# pvbconnector.net
KiCad netlist of a schematic drawn in EAGLE
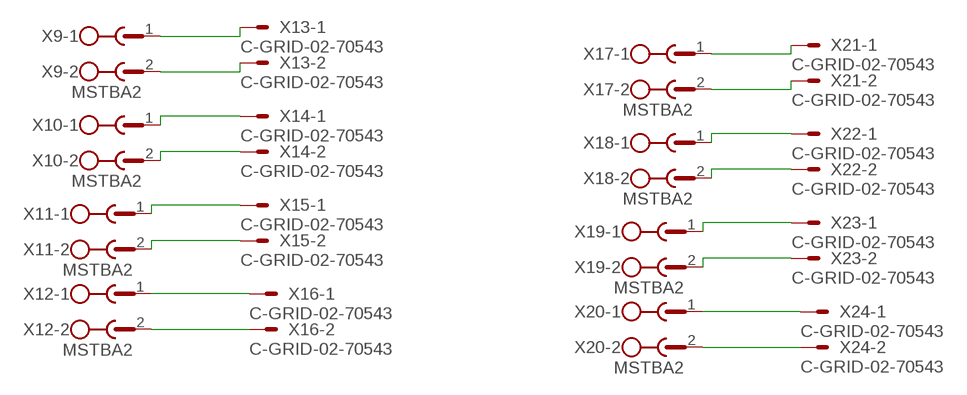
[diagram p0: schematic, sheet 1]

(export (version "E")
  (design (tool "Eeschema 10.0.6"))
  (components
    (comp (ref "X9")
      (value "MSTBA2")
      (footprint "eagle-import:MSTBA2")
      (fields (field (name "MF") "FARNELL") (field (name "MPN") "1757242"))
      (libsource (lib "eagle-import") (part "MSTBA2"))
    )
    (comp (ref "X10")
      (value "MSTBA2")
      (footprint "eagle-import:MSTBA2")
      (fields (field (name "MF") "FARNELL") (field (name "MPN") "1757242"))
      (libsource (lib "eagle-import") (part "MSTBA2"))
    )
    (comp (ref "X11")
      (value "MSTBA2")
      (footprint "eagle-import:MSTBA2")
      (fields (field (name "MF") "FARNELL") (field (name "MPN") "1757242"))
      (libsource (lib "eagle-import") (part "MSTBA2"))
    )
    (comp (ref "X12")
      (value "MSTBA2")
      (footprint "eagle-import:MSTBA2")
      (fields (field (name "MF") "FARNELL") (field (name "MPN") "1757242"))
      (libsource (lib "eagle-import") (part "MSTBA2"))
    )
    (comp (ref "X13")
      (value "C-GRID-02-70543")
      (footprint "eagle-import:70543-02")
      (fields (field (name "MF") "MOLEX"))
      (libsource (lib "eagle-import") (part "C-GRID-02-70543"))
    )
    (comp (ref "X14")
      (value "C-GRID-02-70543")
      (footprint "eagle-import:70543-02")
      (fields (field (name "MF") "MOLEX"))
      (libsource (lib "eagle-import") (part "C-GRID-02-70543"))
    )
    (comp (ref "X15")
      (value "C-GRID-02-70543")
      (footprint "eagle-import:70543-02")
      (fields (field (name "MF") "MOLEX"))
      (libsource (lib "eagle-import") (part "C-GRID-02-70543"))
    )
    (comp (ref "X16")
      (value "C-GRID-02-70543")
      (footprint "eagle-import:70543-02")
      (fields (field (name "MF") "MOLEX"))
      (libsource (lib "eagle-import") (part "C-GRID-02-70543"))
    )
    (comp (ref "X17")
      (value "MSTBA2")
      (footprint "eagle-import:MSTBA2")
      (fields (field (name "MF") "FARNELL") (field (name "MPN") "1757242"))
      (libsource (lib "eagle-import") (part "MSTBA2"))
    )
    (comp (ref "X18")
      (value "MSTBA2")
      (footprint "eagle-import:MSTBA2")
      (fields (field (name "MF") "FARNELL") (field (name "MPN") "1757242"))
      (libsource (lib "eagle-import") (part "MSTBA2"))
    )
    (comp (ref "X19")
      (value "MSTBA2")
      (footprint "eagle-import:MSTBA2")
      (fields (field (name "MF") "FARNELL") (field (name "MPN") "1757242"))
      (libsource (lib "eagle-import") (part "MSTBA2"))
    )
    (comp (ref "X20")
      (value "MSTBA2")
      (footprint "eagle-import:MSTBA2")
      (fields (field (name "MF") "FARNELL") (field (name "MPN") "1757242"))
      (libsource (lib "eagle-import") (part "MSTBA2"))
    )
    (comp (ref "X21")
      (value "C-GRID-02-70543")
      (footprint "eagle-import:70543-02")
      (fields (field (name "MF") "MOLEX"))
      (libsource (lib "eagle-import") (part "C-GRID-02-70543"))
    )
    (comp (ref "X22")
      (value "C-GRID-02-70543")
      (footprint "eagle-import:70543-02")
      (fields (field (name "MF") "MOLEX"))
      (libsource (lib "eagle-import") (part "C-GRID-02-70543"))
    )
    (comp (ref "X23")
      (value "C-GRID-02-70543")
      (footprint "eagle-import:70543-02")
      (fields (field (name "MF") "MOLEX"))
      (libsource (lib "eagle-import") (part "C-GRID-02-70543"))
    )
    (comp (ref "X24")
      (value "C-GRID-02-70543")
      (footprint "eagle-import:70543-02")
      (fields (field (name "MF") "MOLEX"))
      (libsource (lib "eagle-import") (part "C-GRID-02-70543"))
    )
  )
  (nets
    (net (code "1") (name "Net-(X10B-1)") (class "Default")
      (node (ref "X10") (pin "2") (pinfunction "1_2") (pintype "passive"))
      (node (ref "X14") (pin "2") (pinfunction "S_2") (pintype "passive"))
    )
    (net (code "2") (name "Net-(X11B-1)") (class "Default")
      (node (ref "X11") (pin "2") (pinfunction "1_2") (pintype "passive"))
      (node (ref "X15") (pin "2") (pinfunction "S_2") (pintype "passive"))
    )
    (net (code "3") (name "Net-(X12B-1)") (class "Default")
      (node (ref "X12") (pin "2") (pinfunction "1_2") (pintype "passive"))
      (node (ref "X16") (pin "2") (pinfunction "S_2") (pintype "passive"))
    )
    (net (code "4") (name "Net-(X13A-S)") (class "Default")
      (node (ref "X13") (pin "1") (pinfunction "S_1") (pintype "passive"))
      (node (ref "X9") (pin "1") (pinfunction "1_1") (pintype "passive"))
    )
    (net (code "5") (name "Net-(X13B-S)") (class "Default")
      (node (ref "X13") (pin "2") (pinfunction "S_2") (pintype "passive"))
      (node (ref "X9") (pin "2") (pinfunction "1_2") (pintype "passive"))
    )
    (net (code "6") (name "Net-(X14A-S)") (class "Default")
      (node (ref "X10") (pin "1") (pinfunction "1_1") (pintype "passive"))
      (node (ref "X14") (pin "1") (pinfunction "S_1") (pintype "passive"))
    )
    (net (code "7") (name "Net-(X15A-S)") (class "Default")
      (node (ref "X11") (pin "1") (pinfunction "1_1") (pintype "passive"))
      (node (ref "X15") (pin "1") (pinfunction "S_1") (pintype "passive"))
    )
    (net (code "8") (name "Net-(X16A-S)") (class "Default")
      (node (ref "X12") (pin "1") (pinfunction "1_1") (pintype "passive"))
      (node (ref "X16") (pin "1") (pinfunction "S_1") (pintype "passive"))
    )
    (net (code "9") (name "Net-(X17B-1)") (class "Default")
      (node (ref "X17") (pin "2") (pinfunction "1_2") (pintype "passive"))
      (node (ref "X21") (pin "2") (pinfunction "S_2") (pintype "passive"))
    )
    (net (code "10") (name "Net-(X18B-1)") (class "Default")
      (node (ref "X18") (pin "2") (pinfunction "1_2") (pintype "passive"))
      (node (ref "X22") (pin "2") (pinfunction "S_2") (pintype "passive"))
    )
    (net (code "11") (name "Net-(X19B-1)") (class "Default")
      (node (ref "X19") (pin "2") (pinfunction "1_2") (pintype "passive"))
      (node (ref "X23") (pin "2") (pinfunction "S_2") (pintype "passive"))
    )
    (net (code "12") (name "Net-(X20B-1)") (class "Default")
      (node (ref "X20") (pin "2") (pinfunction "1_2") (pintype "passive"))
      (node (ref "X24") (pin "2") (pinfunction "S_2") (pintype "passive"))
    )
    (net (code "13") (name "Net-(X21A-S)") (class "Default")
      (node (ref "X17") (pin "1") (pinfunction "1_1") (pintype "passive"))
      (node (ref "X21") (pin "1") (pinfunction "S_1") (pintype "passive"))
    )
    (net (code "14") (name "Net-(X22A-S)") (class "Default")
      (node (ref "X18") (pin "1") (pinfunction "1_1") (pintype "passive"))
      (node (ref "X22") (pin "1") (pinfunction "S_1") (pintype "passive"))
    )
    (net (code "15") (name "Net-(X23A-S)") (class "Default")
      (node (ref "X19") (pin "1") (pinfunction "1_1") (pintype "passive"))
      (node (ref "X23") (pin "1") (pinfunction "S_1") (pintype "passive"))
    )
    (net (code "16") (name "Net-(X24A-S)") (class "Default")
      (node (ref "X20") (pin "1") (pinfunction "1_1") (pintype "passive"))
      (node (ref "X24") (pin "1") (pinfunction "S_1") (pintype "passive"))
    )
  )
)
